# GO_CART.net
KiCad netlist of a schematic drawn in Altium Designer
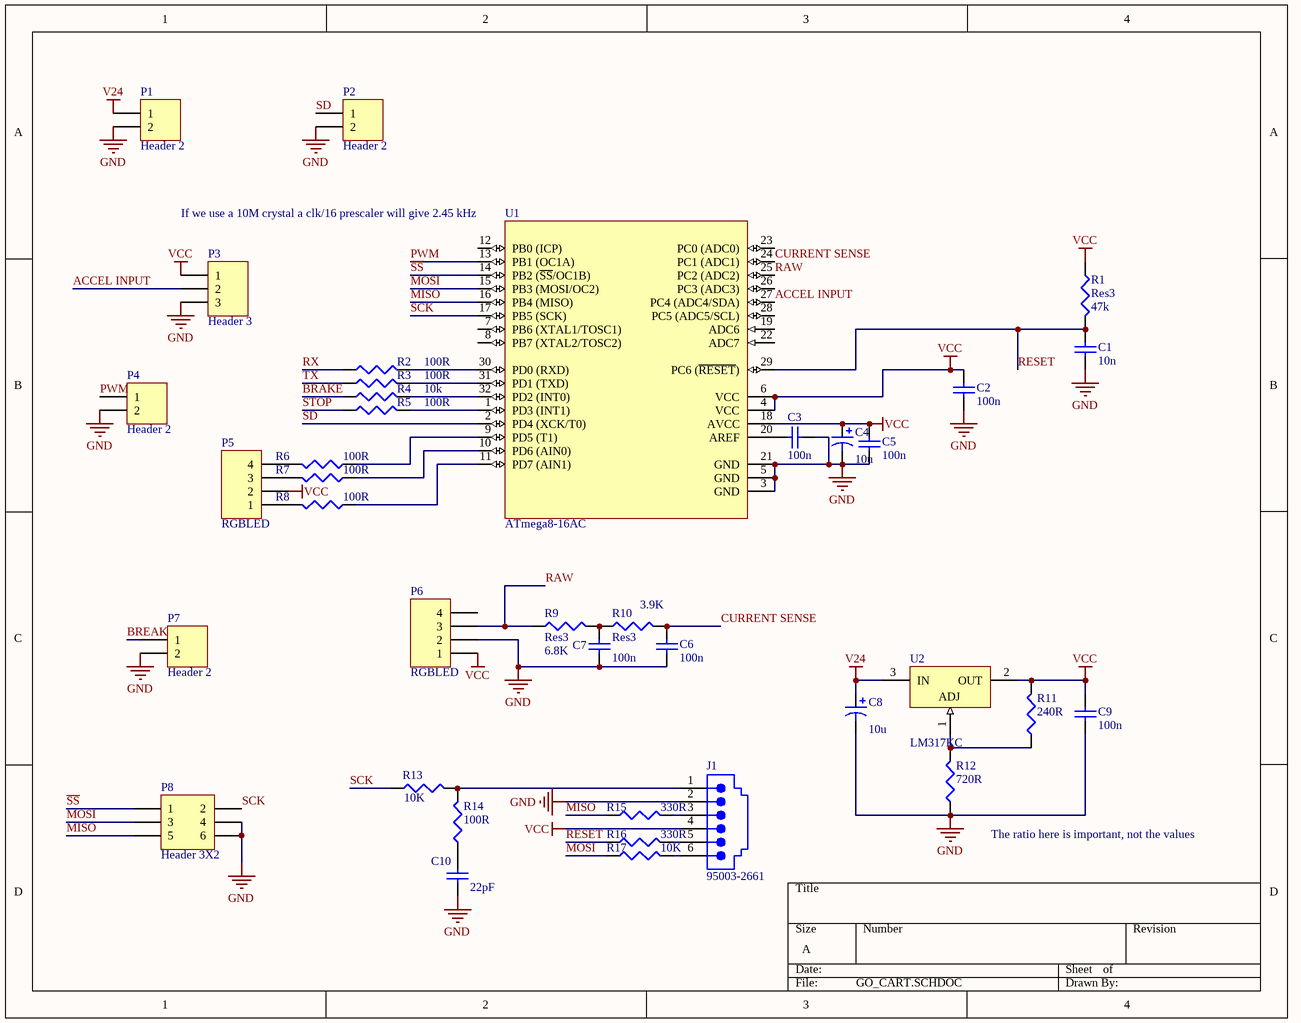
[diagram p0: GO_CART.SCHDOC]

(export (version "E")
  (design (tool "Eeschema 10.0.6"))
  (components
    (comp (ref "C1")
      (value "10n")
      (footprint "AXIAL-0.3")
      (description "Capacitor")
      (fields (field (name "PUBLISHER") "Altium Limited"))
      (libsource (lib "Miscellaneous Devices") (part "Cap"))
    )
    (comp (ref "C2")
      (value "100n")
      (footprint "AXIAL-0.3")
      (description "Capacitor")
      (fields (field (name "PUBLISHER") "Altium Limited"))
      (libsource (lib "Miscellaneous Devices") (part "Cap"))
    )
    (comp (ref "C3")
      (value "100n")
      (footprint "AXIAL-0.3")
      (description "Capacitor")
      (fields (field (name "PUBLISHER") "Altium Limited"))
      (libsource (lib "Miscellaneous Devices") (part "Cap"))
    )
    (comp (ref "C4")
      (value "10u")
      (footprint "B")
      (description "Polarized Capacitor (Radial)")
      (fields (field (name "PUBLISHER") "Altium Limited"))
      (libsource (lib "Miscellaneous Devices") (part "Cap Pol1"))
    )
    (comp (ref "C5")
      (value "100n")
      (footprint "AXIAL-0.3")
      (description "Capacitor")
      (fields (field (name "PUBLISHER") "Altium Limited"))
      (libsource (lib "Miscellaneous Devices") (part "Cap"))
    )
    (comp (ref "C6")
      (value "100n")
      (footprint "AXIAL-0.3")
      (description "Capacitor")
      (fields (field (name "PUBLISHER") "Altium Limited"))
      (libsource (lib "Miscellaneous Devices") (part "Cap"))
    )
    (comp (ref "C7")
      (value "100n")
      (footprint "AXIAL-0.3")
      (description "Capacitor")
      (fields (field (name "PUBLISHER") "Altium Limited"))
      (libsource (lib "Miscellaneous Devices") (part "Cap"))
    )
    (comp (ref "C8")
      (value "10u")
      (footprint "B")
      (description "Polarized Capacitor (Radial)")
      (fields (field (name "PUBLISHER") "Altium Limited"))
      (libsource (lib "Miscellaneous Devices") (part "Cap Pol1"))
    )
    (comp (ref "C9")
      (value "100n")
      (footprint "AXIAL-0.3")
      (description "Capacitor")
      (fields (field (name "PUBLISHER") "Altium Limited"))
      (libsource (lib "Miscellaneous Devices") (part "Cap"))
    )
    (comp (ref "C10")
      (value "22pF")
      (footprint "AXIAL-0.3")
      (description "Capacitor")
      (fields (field (name "PUBLISHER") "Altium Limited"))
      (libsource (lib "Miscellaneous Devices") (part "Cap"))
    )
    (comp (ref "J1")
      (value "95003-2661")
      (footprint "95003-2661")
      (description "Vertical, Standard Profile with Small Panel Cutout PCB Jack")
      (fields (field (name "PUBLISHER") "Altium Limited"))
      (libsource (lib "Molex Modular Jack Vertical") (part "95003-2661"))
    )
    (comp (ref "P1")
      (value "Header 2")
      (footprint "HDR1X2")
      (description "Header, 2-Pin")
      (fields (field (name "PUBLISHER") "Altium Limited"))
      (libsource (lib "Miscellaneous Connectors") (part "Header 2"))
    )
    (comp (ref "P2")
      (value "Header 2")
      (footprint "HDR1X2")
      (description "Header, 2-Pin")
      (fields (field (name "PUBLISHER") "Altium Limited"))
      (libsource (lib "Miscellaneous Connectors") (part "Header 2"))
    )
    (comp (ref "P3")
      (value "Header 3")
      (footprint "HDR1X3")
      (description "Header, 3-Pin")
      (fields (field (name "PUBLISHER") "Altium Limited"))
      (libsource (lib "Miscellaneous Connectors") (part "Header 3"))
    )
    (comp (ref "P4")
      (value "Header 2")
      (footprint "HDR1X2")
      (description "Header, 2-Pin")
      (fields (field (name "PUBLISHER") "Altium Limited"))
      (libsource (lib "Miscellaneous Connectors") (part "Header 2"))
    )
    (comp (ref "P5")
      (value "RGBLED")
      (footprint "HDR1X4")
      (description "Header, 4-Pin")
      (fields (field (name "PUBLISHER") "Altium Limited"))
      (libsource (lib "Miscellaneous Connectors") (part "Header 4"))
    )
    (comp (ref "P6")
      (value "RGBLED")
      (footprint "HDR1X4")
      (description "Header, 4-Pin")
      (fields (field (name "PUBLISHER") "Altium Limited"))
      (libsource (lib "Miscellaneous Connectors") (part "Header 4"))
    )
    (comp (ref "P7")
      (value "Header 2")
      (footprint "HDR1X2")
      (description "Header, 2-Pin")
      (fields (field (name "PUBLISHER") "Altium Limited"))
      (libsource (lib "Miscellaneous Connectors") (part "Header 2"))
    )
    (comp (ref "P8")
      (value "Header 3X2")
      (footprint "HDR2X3")
      (description "Header, 3-Pin, Dual row")
      (fields (field (name "PUBLISHER") "Altium Limited"))
      (libsource (lib "Miscellaneous Connectors") (part "Header 3X2"))
    )
    (comp (ref "R1")
      (value "Res3")
      (footprint "AXIAL-0.4")
      (description "Resistor")
      (fields (field (name "ALTIUM_VALUE") "47k") (field (name "PUBLISHER") "Altium Limited"))
      (libsource (lib "Miscellaneous Devices") (part "Res3"))
    )
    (comp (ref "R2")
      (value "100R")
      (footprint "AXIAL-0.4")
      (description "Resistor")
      (fields (field (name "PUBLISHER") "Altium Limited"))
      (libsource (lib "Miscellaneous Devices") (part "Res3"))
    )
    (comp (ref "R3")
      (value "100R")
      (footprint "AXIAL-0.4")
      (description "Resistor")
      (fields (field (name "PUBLISHER") "Altium Limited"))
      (libsource (lib "Miscellaneous Devices") (part "Res3"))
    )
    (comp (ref "R4")
      (value "10k")
      (footprint "AXIAL-0.4")
      (description "Resistor")
      (fields (field (name "PUBLISHER") "Altium Limited"))
      (libsource (lib "Miscellaneous Devices") (part "Res3"))
    )
    (comp (ref "R5")
      (value "100R")
      (footprint "AXIAL-0.4")
      (description "Resistor")
      (fields (field (name "PUBLISHER") "Altium Limited"))
      (libsource (lib "Miscellaneous Devices") (part "Res3"))
    )
    (comp (ref "R6")
      (value "100R")
      (footprint "AXIAL-0.4")
      (description "Resistor")
      (fields (field (name "Comment") "Res3") (field (name "PUBLISHER") "Altium Limited"))
      (libsource (lib "Miscellaneous Devices") (part "Res3"))
    )
    (comp (ref "R7")
      (value "100R")
      (footprint "AXIAL-0.4")
      (description "Resistor")
      (fields (field (name "Comment") "Res3") (field (name "PUBLISHER") "Altium Limited"))
      (libsource (lib "Miscellaneous Devices") (part "Res3"))
    )
    (comp (ref "R8")
      (value "100R")
      (footprint "AXIAL-0.4")
      (description "Resistor")
      (fields (field (name "Comment") "Res3") (field (name "PUBLISHER") "Altium Limited"))
      (libsource (lib "Miscellaneous Devices") (part "Res3"))
    )
    (comp (ref "R9")
      (value "Res3")
      (footprint "AXIAL-0.4")
      (description "Resistor")
      (fields (field (name "ALTIUM_VALUE") "6.8K") (field (name "PUBLISHER") "Altium Limited"))
      (libsource (lib "Miscellaneous Devices") (part "Res3"))
    )
    (comp (ref "R10")
      (value "Res3")
      (footprint "AXIAL-0.4")
      (description "Resistor")
      (fields (field (name "ALTIUM_VALUE") "3.9K") (field (name "PUBLISHER") "Altium Limited"))
      (libsource (lib "Miscellaneous Devices") (part "Res3"))
    )
    (comp (ref "R11")
      (value "240R")
      (footprint "AXIAL-0.4")
      (description "Resistor")
      (fields (field (name "Comment") "Res3") (field (name "PUBLISHER") "Altium Limited"))
      (libsource (lib "Miscellaneous Devices") (part "Res3"))
    )
    (comp (ref "R12")
      (value "720R")
      (footprint "AXIAL-0.4")
      (description "Resistor")
      (fields (field (name "Comment") "Res3") (field (name "PUBLISHER") "Altium Limited"))
      (libsource (lib "Miscellaneous Devices") (part "Res3"))
    )
    (comp (ref "R13")
      (value "10K")
      (footprint "AXIAL-0.4")
      (description "Resistor")
      (fields (field (name "Comment") "Res3") (field (name "PUBLISHER") "Altium Limited"))
      (libsource (lib "Miscellaneous Devices") (part "Res3"))
    )
    (comp (ref "R14")
      (value "100R")
      (footprint "AXIAL-0.4")
      (description "Resistor")
      (fields (field (name "Comment") "Res3") (field (name "PUBLISHER") "Altium Limited"))
      (libsource (lib "Miscellaneous Devices") (part "Res3"))
    )
    (comp (ref "R15")
      (value "330R")
      (footprint "AXIAL-0.4")
      (description "Resistor")
      (fields (field (name "Comment") "Res3") (field (name "PUBLISHER") "Altium Limited"))
      (libsource (lib "Miscellaneous Devices") (part "Res3"))
    )
    (comp (ref "R16")
      (value "330R")
      (footprint "AXIAL-0.4")
      (description "Resistor")
      (fields (field (name "Comment") "Res3") (field (name "PUBLISHER") "Altium Limited"))
      (libsource (lib "Miscellaneous Devices") (part "Res3"))
    )
    (comp (ref "R17")
      (value "10K")
      (footprint "AXIAL-0.4")
      (description "Resistor")
      (fields (field (name "Comment") "Res3") (field (name "PUBLISHER") "Altium Limited"))
      (libsource (lib "Miscellaneous Devices") (part "Res3"))
    )
    (comp (ref "U1")
      (value "ATmega8-16AC")
      (footprint "32A_N")
      (description "8-Bit AVR Microcontroller with 8K Bytes of In-System Programmable Flash Memory")
      (fields (field (name "PUBLISHER") "Altium Limited"))
      (libsource (lib "Atmel Microcontroller 8-Bit AVR") (part "ATmega8-16AC"))
    )
    (comp (ref "U2")
      (value "LM317KC")
      (footprint "KC03")
      (description "3-Terminal Adjustable Regulator")
      (fields (field (name "PUBLISHER") "Altium Limited"))
      (libsource (lib "TI Power Mgt Voltage Regulator") (part "LM317KC"))
    )
  )
  (nets
    (net (code "1") (name "/ACCEL INPUT") (class "Default")
      (node (ref "P3") (pin "2") (pinfunction "2_2") (pintype "passive"))
      (node (ref "U1") (pin "27") (pinfunction "PC4_(ADC4/SDA)_27") (pintype "bidirectional"))
    )
    (net (code "2") (name "/BRAKE") (class "Default")
      (node (ref "R4") (pin "1") (pinfunction "1_1") (pintype "passive"))
    )
    (net (code "3") (name "/BREAK") (class "Default")
      (node (ref "P7") (pin "1") (pinfunction "1_1") (pintype "passive"))
    )
    (net (code "4") (name "/CURRENT SENSE") (class "Default")
      (node (ref "C6") (pin "1") (pinfunction "1_1") (pintype "passive"))
      (node (ref "R10") (pin "2") (pinfunction "2_2") (pintype "passive"))
      (node (ref "U1") (pin "24") (pinfunction "PC1_(ADC1)_24") (pintype "bidirectional"))
    )
    (net (code "5") (name "/MISO") (class "Default")
      (node (ref "P8") (pin "5") (pinfunction "5_5") (pintype "passive"))
      (node (ref "R15") (pin "1") (pinfunction "1_1") (pintype "passive"))
      (node (ref "U1") (pin "16") (pinfunction "PB4_(MISO)_16") (pintype "bidirectional"))
    )
    (net (code "6") (name "/MOSI") (class "Default")
      (node (ref "P8") (pin "3") (pinfunction "3_3") (pintype "passive"))
      (node (ref "R17") (pin "1") (pinfunction "1_1") (pintype "passive"))
      (node (ref "U1") (pin "15") (pinfunction "PB3_(MOSI/OC2)_15") (pintype "bidirectional"))
    )
    (net (code "7") (name "/PWM") (class "Default")
      (node (ref "P4") (pin "1") (pinfunction "1_1") (pintype "passive"))
      (node (ref "U1") (pin "13") (pinfunction "PB1_(OC1A)_13") (pintype "bidirectional"))
    )
    (net (code "8") (name "/RAW") (class "Default")
      (node (ref "P6") (pin "3") (pinfunction "3_3") (pintype "passive"))
      (node (ref "R9") (pin "1") (pinfunction "1_1") (pintype "passive"))
      (node (ref "U1") (pin "25") (pinfunction "PC2_(ADC2)_25") (pintype "bidirectional"))
    )
    (net (code "9") (name "/RESET") (class "Default")
      (node (ref "C1") (pin "1") (pinfunction "1_1") (pintype "passive"))
      (node (ref "R1") (pin "2") (pinfunction "2_2") (pintype "passive"))
      (node (ref "R16") (pin "1") (pinfunction "1_1") (pintype "passive"))
      (node (ref "U1") (pin "29") (pinfunction "PC6_(~{RESET})_29") (pintype "bidirectional"))
    )
    (net (code "10") (name "/RX") (class "Default")
      (node (ref "R2") (pin "1") (pinfunction "1_1") (pintype "passive"))
    )
    (net (code "11") (name "/SCK") (class "Default")
      (node (ref "P8") (pin "2") (pinfunction "2_2") (pintype "passive"))
      (node (ref "R13") (pin "1") (pinfunction "1_1") (pintype "passive"))
      (node (ref "U1") (pin "17") (pinfunction "PB5_(SCK)_17") (pintype "bidirectional"))
    )
    (net (code "12") (name "/SD") (class "Default")
      (node (ref "P2") (pin "1") (pinfunction "1_1") (pintype "passive"))
      (node (ref "U1") (pin "2") (pinfunction "PD4_(XCK/T0)_2") (pintype "bidirectional"))
    )
    (net (code "13") (name "/STOP") (class "Default")
      (node (ref "R5") (pin "1") (pinfunction "1_1") (pintype "passive"))
    )
    (net (code "14") (name "/TX") (class "Default")
      (node (ref "R3") (pin "1") (pinfunction "1_1") (pintype "passive"))
    )
    (net (code "15") (name "/~{SS}") (class "Default")
      (node (ref "P8") (pin "1") (pinfunction "1_1") (pintype "passive"))
      (node (ref "U1") (pin "14") (pinfunction "PB2_(~{SS}/OC1B)_14") (pintype "bidirectional"))
    )
    (net (code "16") (name "GND") (class "Default")
      (node (ref "C1") (pin "2") (pinfunction "2_2") (pintype "passive"))
      (node (ref "C10") (pin "2") (pinfunction "2_2") (pintype "passive"))
      (node (ref "C2") (pin "2") (pinfunction "2_2") (pintype "passive"))
      (node (ref "C3") (pin "1") (pinfunction "1_1") (pintype "passive"))
      (node (ref "C4") (pin "2") (pinfunction "2_2") (pintype "passive"))
      (node (ref "C5") (pin "2") (pinfunction "2_2") (pintype "passive"))
      (node (ref "C6") (pin "2") (pinfunction "2_2") (pintype "passive"))
      (node (ref "C7") (pin "2") (pinfunction "2_2") (pintype "passive"))
      (node (ref "C8") (pin "2") (pinfunction "2_2") (pintype "passive"))
      (node (ref "C9") (pin "2") (pinfunction "2_2") (pintype "passive"))
      (node (ref "J1") (pin "2") (pinfunction "2_2") (pintype "passive"))
      (node (ref "P1") (pin "2") (pinfunction "2_2") (pintype "passive"))
      (node (ref "P2") (pin "2") (pinfunction "2_2") (pintype "passive"))
      (node (ref "P3") (pin "3") (pinfunction "3_3") (pintype "passive"))
      (node (ref "P4") (pin "2") (pinfunction "2_2") (pintype "passive"))
      (node (ref "P6") (pin "2") (pinfunction "2_2") (pintype "passive"))
      (node (ref "P7") (pin "2") (pinfunction "2_2") (pintype "passive"))
      (node (ref "P8") (pin "4") (pinfunction "4_4") (pintype "passive"))
      (node (ref "P8") (pin "6") (pinfunction "6_6") (pintype "passive"))
      (node (ref "R12") (pin "1") (pinfunction "1_1") (pintype "passive"))
      (node (ref "U1") (pin "21") (pinfunction "GND_21") (pintype "power_in"))
      (node (ref "U1") (pin "3") (pinfunction "GND_3") (pintype "power_in"))
      (node (ref "U1") (pin "5") (pinfunction "GND_5") (pintype "power_in"))
    )
    (net (code "17") (name "Net-(C7-Pad1)") (class "Default")
      (node (ref "C7") (pin "1") (pinfunction "1_1") (pintype "passive"))
      (node (ref "R10") (pin "1") (pinfunction "1_1") (pintype "passive"))
      (node (ref "R9") (pin "2") (pinfunction "2_2") (pintype "passive"))
    )
    (net (code "18") (name "Net-(C10-Pad1)") (class "Default")
      (node (ref "C10") (pin "1") (pinfunction "1_1") (pintype "passive"))
      (node (ref "R14") (pin "1") (pinfunction "1_1") (pintype "passive"))
    )
    (net (code "19") (name "Net-(J1-Pad1)") (class "Default")
      (node (ref "J1") (pin "1") (pinfunction "1_1") (pintype "passive"))
      (node (ref "R13") (pin "2") (pinfunction "2_2") (pintype "passive"))
      (node (ref "R14") (pin "2") (pinfunction "2_2") (pintype "passive"))
    )
    (net (code "20") (name "Net-(J1-Pad3)") (class "Default")
      (node (ref "J1") (pin "3") (pinfunction "3_3") (pintype "passive"))
      (node (ref "R15") (pin "2") (pinfunction "2_2") (pintype "passive"))
    )
    (net (code "21") (name "Net-(J1-Pad5)") (class "Default")
      (node (ref "J1") (pin "5") (pinfunction "5_5") (pintype "passive"))
      (node (ref "R16") (pin "2") (pinfunction "2_2") (pintype "passive"))
    )
    (net (code "22") (name "Net-(J1-Pad6)") (class "Default")
      (node (ref "J1") (pin "6") (pinfunction "6_6") (pintype "passive"))
      (node (ref "R17") (pin "2") (pinfunction "2_2") (pintype "passive"))
    )
    (net (code "23") (name "Net-(P5-Pad1)") (class "Default")
      (node (ref "P5") (pin "1") (pinfunction "1_1") (pintype "passive"))
      (node (ref "R8") (pin "2") (pinfunction "2_2") (pintype "passive"))
    )
    (net (code "24") (name "Net-(P5-Pad3)") (class "Default")
      (node (ref "P5") (pin "3") (pinfunction "3_3") (pintype "passive"))
      (node (ref "R7") (pin "2") (pinfunction "2_2") (pintype "passive"))
    )
    (net (code "25") (name "Net-(P5-Pad4)") (class "Default")
      (node (ref "P5") (pin "4") (pinfunction "4_4") (pintype "passive"))
      (node (ref "R6") (pin "2") (pinfunction "2_2") (pintype "passive"))
    )
    (net (code "26") (name "Net-(U1-AREF)") (class "Default")
      (node (ref "C3") (pin "2") (pinfunction "2_2") (pintype "passive"))
      (node (ref "U1") (pin "20") (pinfunction "AREF_20") (pintype "passive"))
    )
    (net (code "27") (name "Net-(U1-PD0_(RXD))") (class "Default")
      (node (ref "R2") (pin "2") (pinfunction "2_2") (pintype "passive"))
      (node (ref "U1") (pin "30") (pinfunction "PD0_(RXD)_30") (pintype "bidirectional"))
    )
    (net (code "28") (name "Net-(U1-PD1_(TXD))") (class "Default")
      (node (ref "R3") (pin "2") (pinfunction "2_2") (pintype "passive"))
      (node (ref "U1") (pin "31") (pinfunction "PD1_(TXD)_31") (pintype "bidirectional"))
    )
    (net (code "29") (name "Net-(U1-PD2_(INT0))") (class "Default")
      (node (ref "R4") (pin "2") (pinfunction "2_2") (pintype "passive"))
      (node (ref "U1") (pin "32") (pinfunction "PD2_(INT0)_32") (pintype "bidirectional"))
    )
    (net (code "30") (name "Net-(U1-PD3_(INT1))") (class "Default")
      (node (ref "R5") (pin "2") (pinfunction "2_2") (pintype "passive"))
      (node (ref "U1") (pin "1") (pinfunction "PD3_(INT1)_1") (pintype "bidirectional"))
    )
    (net (code "31") (name "Net-(U1-PD5_(T1))") (class "Default")
      (node (ref "R6") (pin "1") (pinfunction "1_1") (pintype "passive"))
      (node (ref "U1") (pin "9") (pinfunction "PD5_(T1)_9") (pintype "bidirectional"))
    )
    (net (code "32") (name "Net-(U1-PD6_(AIN0))") (class "Default")
      (node (ref "R7") (pin "1") (pinfunction "1_1") (pintype "passive"))
      (node (ref "U1") (pin "10") (pinfunction "PD6_(AIN0)_10") (pintype "bidirectional"))
    )
    (net (code "33") (name "Net-(U1-PD7_(AIN1))") (class "Default")
      (node (ref "R8") (pin "1") (pinfunction "1_1") (pintype "passive"))
      (node (ref "U1") (pin "11") (pinfunction "PD7_(AIN1)_11") (pintype "bidirectional"))
    )
    (net (code "34") (name "Net-(U2-ADJ)") (class "Default")
      (node (ref "R11") (pin "1") (pinfunction "1_1") (pintype "passive"))
      (node (ref "R12") (pin "2") (pinfunction "2_2") (pintype "passive"))
      (node (ref "U2") (pin "1") (pinfunction "ADJ_1") (pintype "input"))
    )
    (net (code "35") (name "V24") (class "Default")
      (node (ref "C8") (pin "1") (pinfunction "1_1") (pintype "passive"))
      (node (ref "P1") (pin "1") (pinfunction "1_1") (pintype "passive"))
      (node (ref "U2") (pin "3") (pinfunction "IN_3") (pintype "power_in"))
    )
    (net (code "36") (name "VCC") (class "Default")
      (node (ref "C2") (pin "1") (pinfunction "1_1") (pintype "passive"))
      (node (ref "C4") (pin "1") (pinfunction "1_1") (pintype "passive"))
      (node (ref "C5") (pin "1") (pinfunction "1_1") (pintype "passive"))
      (node (ref "C9") (pin "1") (pinfunction "1_1") (pintype "passive"))
      (node (ref "J1") (pin "4") (pinfunction "4_4") (pintype "passive"))
      (node (ref "P3") (pin "1") (pinfunction "1_1") (pintype "passive"))
      (node (ref "P5") (pin "2") (pinfunction "2_2") (pintype "passive"))
      (node (ref "P6") (pin "1") (pinfunction "1_1") (pintype "passive"))
      (node (ref "R1") (pin "1") (pinfunction "1_1") (pintype "passive"))
      (node (ref "R11") (pin "2") (pinfunction "2_2") (pintype "passive"))
      (node (ref "U1") (pin "18") (pinfunction "AVCC_18") (pintype "power_in"))
      (node (ref "U1") (pin "4") (pinfunction "VCC_4") (pintype "power_in"))
      (node (ref "U1") (pin "6") (pinfunction "VCC_6") (pintype "power_in"))
      (node (ref "U2") (pin "2") (pinfunction "OUT_2") (pintype "power_in"))
    )
    (net (code "37") (name "unconnected-(P6-Pad4)") (class "Default")
      (node (ref "P6") (pin "4") (pinfunction "4_4") (pintype "passive"))
    )
    (net (code "38") (name "unconnected-(U1-ADC6-Pad19)") (class "Default")
      (node (ref "U1") (pin "19") (pinfunction "ADC6_19") (pintype "input"))
    )
    (net (code "39") (name "unconnected-(U1-ADC7-Pad22)") (class "Default")
      (node (ref "U1") (pin "22") (pinfunction "ADC7_22") (pintype "input"))
    )
    (net (code "40") (name "unconnected-(U1-PB0_(ICP)-Pad12)") (class "Default")
      (node (ref "U1") (pin "12") (pinfunction "PB0_(ICP)_12") (pintype "bidirectional"))
    )
    (net (code "41") (name "unconnected-(U1-PB6_(XTAL1{slash}TOSC1)-Pad7)") (class "Default")
      (node (ref "U1") (pin "7") (pinfunction "PB6_(XTAL1/TOSC1)_7") (pintype "bidirectional"))
    )
    (net (code "42") (name "unconnected-(U1-PB7_(XTAL2{slash}TOSC2)-Pad8)") (class "Default")
      (node (ref "U1") (pin "8") (pinfunction "PB7_(XTAL2/TOSC2)_8") (pintype "bidirectional"))
    )
    (net (code "43") (name "unconnected-(U1-PC0_(ADC0)-Pad23)") (class "Default")
      (node (ref "U1") (pin "23") (pinfunction "PC0_(ADC0)_23") (pintype "bidirectional"))
    )
    (net (code "44") (name "unconnected-(U1-PC3_(ADC3)-Pad26)") (class "Default")
      (node (ref "U1") (pin "26") (pinfunction "PC3_(ADC3)_26") (pintype "bidirectional"))
    )
    (net (code "45") (name "unconnected-(U1-PC5_(ADC5{slash}SCL)-Pad28)") (class "Default")
      (node (ref "U1") (pin "28") (pinfunction "PC5_(ADC5/SCL)_28") (pintype "bidirectional"))
    )
  )
)
